# 02_Beam_Inputs.net
KiCad netlist of a schematic drawn in Altium Designer
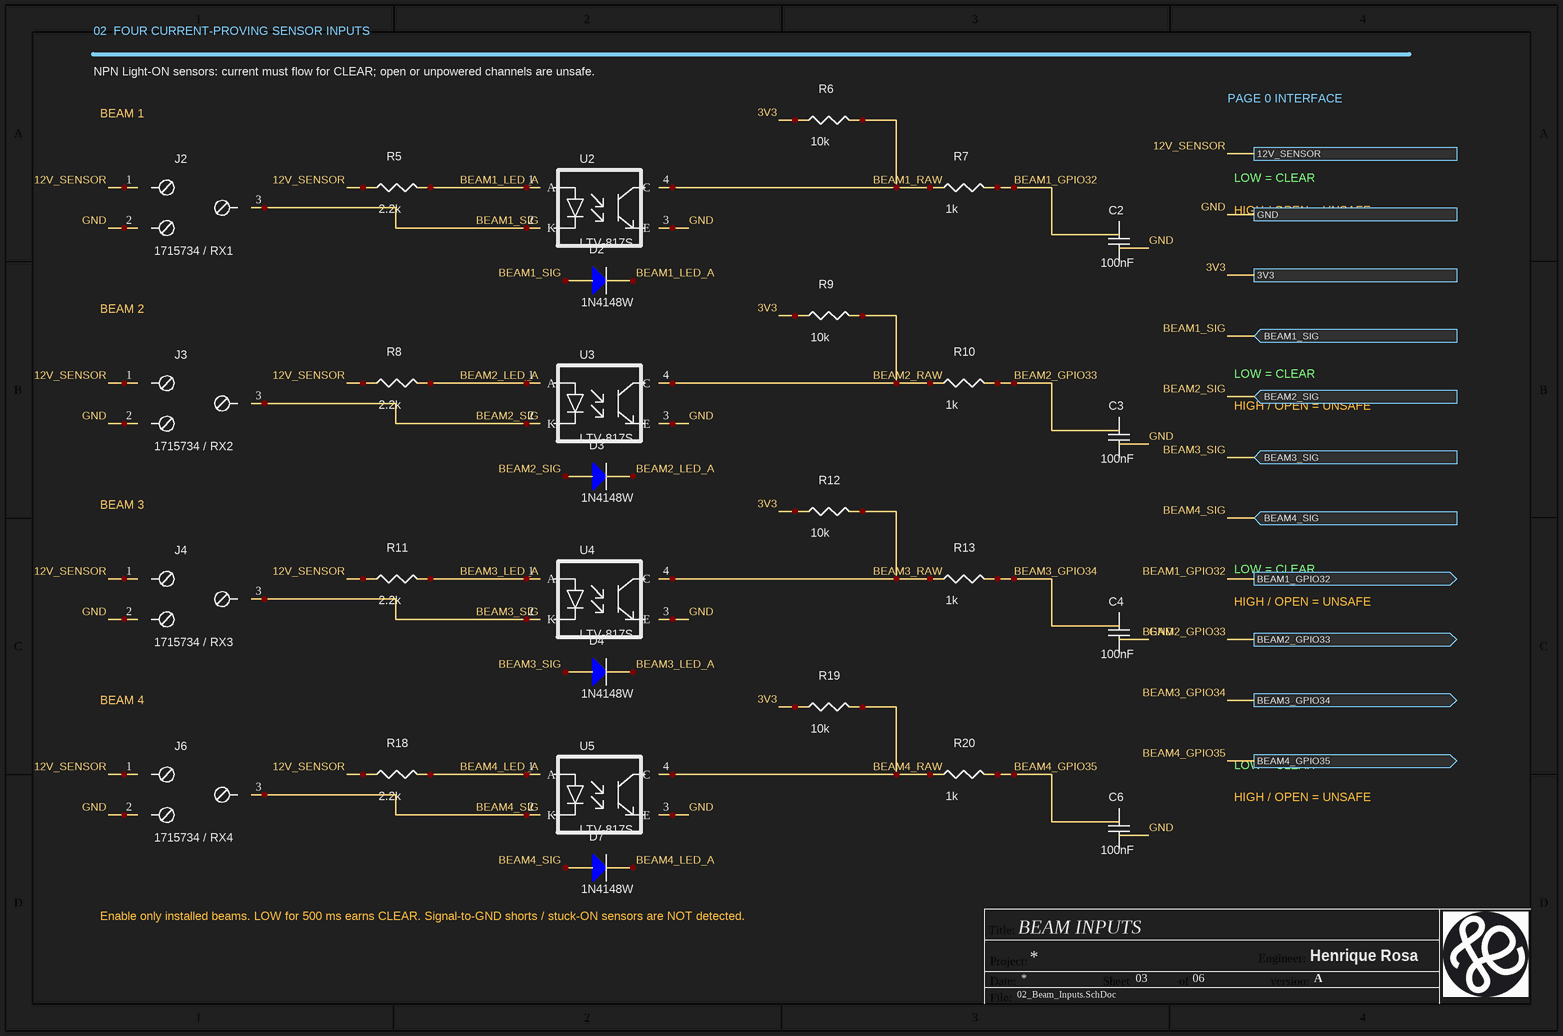
[diagram p0: 02_Beam_Inputs.SchDoc]

(export (version "E")
  (design (tool "Eeschema 10.0.6"))
  (components
    (comp (ref "C2")
      (value "100nF")
      (footprint "PCB - CAPACITOR - MLCC - MURATA GRM21B 0805_2012:MURATA GRM21B 0805_2012")
      (description "Input RC filter")
      (fields
        (field (name "MANUFACTURER") "Murata")
        (field (name "MANUFACTURER PART NUMBER") "GRM21BR71H104KA01L")
      )
      (libsource (lib "Miscellaneous Devices") (part "GRM21BR71H104KA01L"))
    )
    (comp (ref "C3")
      (value "100nF")
      (footprint "PCB - CAPACITOR - MLCC - MURATA GRM21B 0805_2012:MURATA GRM21B 0805_2012")
      (description "Input RC filter")
      (fields
        (field (name "MANUFACTURER") "Murata")
        (field (name "MANUFACTURER PART NUMBER") "GRM21BR71H104KA01L")
      )
      (libsource (lib "Miscellaneous Devices") (part "GRM21BR71H104KA01L"))
    )
    (comp (ref "C4")
      (value "100nF")
      (footprint "PCB - CAPACITOR - MLCC - MURATA GRM21B 0805_2012:MURATA GRM21B 0805_2012")
      (description "Input RC filter")
      (fields
        (field (name "MANUFACTURER") "Murata")
        (field (name "MANUFACTURER PART NUMBER") "GRM21BR71H104KA01L")
      )
      (libsource (lib "Miscellaneous Devices") (part "GRM21BR71H104KA01L"))
    )
    (comp (ref "C6")
      (value "100nF")
      (footprint "PCB - CAPACITOR - MLCC - MURATA GRM21B 0805_2012:MURATA GRM21B 0805_2012")
      (description "Input RC filter")
      (fields
        (field (name "MANUFACTURER") "Murata")
        (field (name "MANUFACTURER PART NUMBER") "GRM21BR71H104KA01L")
      )
      (libsource (lib "Miscellaneous Devices") (part "GRM21BR71H104KA01L"))
    )
    (comp (ref "D2")
      (value "1N4148W")
      (footprint "PinRepairFootprints:1N4148W_SOD123_A1_K2")
      (description "Reverse clamp: A to SIG; K to opto LED anode")
      (fields (field (name "PART NUMBER") "FDLL4148") (field (name "MANUFACTURER") "Nexperia"))
      (libsource (lib "Miscellaneous Devices") (part "1N4148W"))
    )
    (comp (ref "D3")
      (value "1N4148W")
      (footprint "PinRepairFootprints:1N4148W_SOD123_A1_K2")
      (description "Reverse clamp: A to SIG; K to opto LED anode")
      (fields (field (name "PART NUMBER") "FDLL4148") (field (name "MANUFACTURER") "Nexperia"))
      (libsource (lib "Miscellaneous Devices") (part "1N4148W"))
    )
    (comp (ref "D4")
      (value "1N4148W")
      (footprint "PinRepairFootprints:1N4148W_SOD123_A1_K2")
      (description "Reverse clamp: A to SIG; K to opto LED anode")
      (fields (field (name "PART NUMBER") "FDLL4148") (field (name "MANUFACTURER") "Nexperia"))
      (libsource (lib "Miscellaneous Devices") (part "1N4148W"))
    )
    (comp (ref "D7")
      (value "1N4148W")
      (footprint "PinRepairFootprints:1N4148W_SOD123_A1_K2")
      (description "Reverse clamp: A to SIG; K to opto LED anode")
      (fields (field (name "PART NUMBER") "FDLL4148") (field (name "MANUFACTURER") "Nexperia"))
      (libsource (lib "Miscellaneous Devices") (part "1N4148W"))
    )
    (comp (ref "J2")
      (value "1715734 / RX1")
      (footprint "OpticalHardware:PHOENIX_1715734_MKDS_3_508")
      (description "12V / GND / NPN signal terminal")
      (fields
        (field (name "MANUFACTURER") "Phoenix Contact")
        (field (name "MANUFACTURER PART NUMBER") "1715734")
      )
      (libsource (lib "PartSpecificComponents") (part "PHOENIX_1715734"))
    )
    (comp (ref "J3")
      (value "1715734 / RX2")
      (footprint "OpticalHardware:PHOENIX_1715734_MKDS_3_508")
      (description "12V / GND / NPN signal terminal")
      (fields
        (field (name "MANUFACTURER") "Phoenix Contact")
        (field (name "MANUFACTURER PART NUMBER") "1715734")
      )
      (libsource (lib "PartSpecificComponents") (part "PHOENIX_1715734"))
    )
    (comp (ref "J4")
      (value "1715734 / RX3")
      (footprint "OpticalHardware:PHOENIX_1715734_MKDS_3_508")
      (description "12V / GND / NPN signal terminal")
      (fields
        (field (name "MANUFACTURER") "Phoenix Contact")
        (field (name "MANUFACTURER PART NUMBER") "1715734")
      )
      (libsource (lib "PartSpecificComponents") (part "PHOENIX_1715734"))
    )
    (comp (ref "J6")
      (value "1715734 / RX4")
      (footprint "OpticalHardware:PHOENIX_1715734_MKDS_3_508")
      (description "12V / GND / NPN signal terminal")
      (fields
        (field (name "MANUFACTURER") "Phoenix Contact")
        (field (name "MANUFACTURER PART NUMBER") "1715734")
      )
      (libsource (lib "PartSpecificComponents") (part "PHOENIX_1715734"))
    )
    (comp (ref "R5")
      (value "2.2k")
      (footprint "PCB - RESISTOR - CHIP - YAGEO RES 0805_2012:YAGEO RES 0805_2012")
      (description "Optocoupler LED current limit")
      (fields
        (field (name "MANUFACTURER") "Yageo")
        (field (name "MANUFACTURER PART NUMBER") "RC0805FR-072K2L")
      )
      (libsource (lib "Miscellaneous Devices") (part "RC0805FR-072K2L"))
    )
    (comp (ref "R6")
      (value "10k")
      (footprint "PCB - RESISTOR - CHIP - YAGEO RES 0805_2012:YAGEO RES 0805_2012")
      (description "Pull-up earns unsafe if optocoupler is off")
      (fields
        (field (name "MANUFACTURER") "Yageo")
        (field (name "MANUFACTURER PART NUMBER") "RC0805FR-0710KL")
      )
      (libsource (lib "Miscellaneous Devices") (part "RC0805FR-0710KL"))
    )
    (comp (ref "R7")
      (value "1k")
      (footprint "PCB - RESISTOR - CHIP - YAGEO RES 0805_2012:YAGEO RES 0805_2012")
      (description "Input current limit")
      (fields
        (field (name "MANUFACTURER") "Yageo")
        (field (name "MANUFACTURER PART NUMBER") "RC0805FR-071KL")
      )
      (libsource (lib "Miscellaneous Devices") (part "RC0805FR-071KL"))
    )
    (comp (ref "R8")
      (value "2.2k")
      (footprint "PCB - RESISTOR - CHIP - YAGEO RES 0805_2012:YAGEO RES 0805_2012")
      (description "Optocoupler LED current limit")
      (fields
        (field (name "MANUFACTURER") "Yageo")
        (field (name "MANUFACTURER PART NUMBER") "RC0805FR-072K2L")
      )
      (libsource (lib "Miscellaneous Devices") (part "RC0805FR-072K2L"))
    )
    (comp (ref "R9")
      (value "10k")
      (footprint "PCB - RESISTOR - CHIP - YAGEO RES 0805_2012:YAGEO RES 0805_2012")
      (description "Pull-up earns unsafe if optocoupler is off")
      (fields
        (field (name "MANUFACTURER") "Yageo")
        (field (name "MANUFACTURER PART NUMBER") "RC0805FR-0710KL")
      )
      (libsource (lib "Miscellaneous Devices") (part "RC0805FR-0710KL"))
    )
    (comp (ref "R10")
      (value "1k")
      (footprint "PCB - RESISTOR - CHIP - YAGEO RES 0805_2012:YAGEO RES 0805_2012")
      (description "Input current limit")
      (fields
        (field (name "MANUFACTURER") "Yageo")
        (field (name "MANUFACTURER PART NUMBER") "RC0805FR-071KL")
      )
      (libsource (lib "Miscellaneous Devices") (part "RC0805FR-071KL"))
    )
    (comp (ref "R11")
      (value "2.2k")
      (footprint "PCB - RESISTOR - CHIP - YAGEO RES 0805_2012:YAGEO RES 0805_2012")
      (description "Optocoupler LED current limit")
      (fields
        (field (name "MANUFACTURER") "Yageo")
        (field (name "MANUFACTURER PART NUMBER") "RC0805FR-072K2L")
      )
      (libsource (lib "Miscellaneous Devices") (part "RC0805FR-072K2L"))
    )
    (comp (ref "R12")
      (value "10k")
      (footprint "PCB - RESISTOR - CHIP - YAGEO RES 0805_2012:YAGEO RES 0805_2012")
      (description "Pull-up earns unsafe if optocoupler is off")
      (fields
        (field (name "MANUFACTURER") "Yageo")
        (field (name "MANUFACTURER PART NUMBER") "RC0805FR-0710KL")
      )
      (libsource (lib "Miscellaneous Devices") (part "RC0805FR-0710KL"))
    )
    (comp (ref "R13")
      (value "1k")
      (footprint "PCB - RESISTOR - CHIP - YAGEO RES 0805_2012:YAGEO RES 0805_2012")
      (description "Input current limit")
      (fields
        (field (name "MANUFACTURER") "Yageo")
        (field (name "MANUFACTURER PART NUMBER") "RC0805FR-071KL")
      )
      (libsource (lib "Miscellaneous Devices") (part "RC0805FR-071KL"))
    )
    (comp (ref "R18")
      (value "2.2k")
      (footprint "PCB - RESISTOR - CHIP - YAGEO RES 0805_2012:YAGEO RES 0805_2012")
      (description "Optocoupler LED current limit")
      (fields
        (field (name "MANUFACTURER") "Yageo")
        (field (name "MANUFACTURER PART NUMBER") "RC0805FR-072K2L")
      )
      (libsource (lib "Miscellaneous Devices") (part "RC0805FR-072K2L"))
    )
    (comp (ref "R19")
      (value "10k")
      (footprint "PCB - RESISTOR - CHIP - YAGEO RES 0805_2012:YAGEO RES 0805_2012")
      (description "Pull-up earns unsafe if optocoupler is off")
      (fields
        (field (name "MANUFACTURER") "Yageo")
        (field (name "MANUFACTURER PART NUMBER") "RC0805FR-0710KL")
      )
      (libsource (lib "Miscellaneous Devices") (part "RC0805FR-0710KL"))
    )
    (comp (ref "R20")
      (value "1k")
      (footprint "PCB - RESISTOR - CHIP - YAGEO RES 0805_2012:YAGEO RES 0805_2012")
      (description "Input current limit")
      (fields
        (field (name "MANUFACTURER") "Yageo")
        (field (name "MANUFACTURER PART NUMBER") "RC0805FR-071KL")
      )
      (libsource (lib "Miscellaneous Devices") (part "RC0805FR-071KL"))
    )
    (comp (ref "U2")
      (value "LTV-817S")
      (footprint "PCB - OPTOISOLATOR - LITEON LTV-817:LITEON LTV-817")
      (description "Phototransistor optocoupler")
      (fields
        (field (name "MANUFACTURER") "Lite-On")
        (field (name "MANUFACTURER PART NUMBER") "LTV-817S-TA1")
      )
      (libsource (lib "*") (part "LTV-817S-TA1"))
    )
    (comp (ref "U3")
      (value "LTV-817S")
      (footprint "PCB - OPTOISOLATOR - LITEON LTV-817:LITEON LTV-817")
      (description "Phototransistor optocoupler")
      (fields
        (field (name "MANUFACTURER") "Lite-On")
        (field (name "MANUFACTURER PART NUMBER") "LTV-817S-TA1")
      )
      (libsource (lib "*") (part "LTV-817S-TA1"))
    )
    (comp (ref "U4")
      (value "LTV-817S")
      (footprint "PCB - OPTOISOLATOR - LITEON LTV-817:LITEON LTV-817")
      (description "Phototransistor optocoupler")
      (fields
        (field (name "MANUFACTURER") "Lite-On")
        (field (name "MANUFACTURER PART NUMBER") "LTV-817S-TA1")
      )
      (libsource (lib "*") (part "LTV-817S-TA1"))
    )
    (comp (ref "U5")
      (value "LTV-817S")
      (footprint "PCB - OPTOISOLATOR - LITEON LTV-817:LITEON LTV-817")
      (description "Phototransistor optocoupler")
      (fields
        (field (name "MANUFACTURER") "Lite-On")
        (field (name "MANUFACTURER PART NUMBER") "LTV-817S-TA1")
      )
      (libsource (lib "*") (part "LTV-817S-TA1"))
    )
  )
  (nets
    (net (code "1") (name "/3V3") (class "Default")
      (node (ref "R12") (pin "1") (pinfunction "1_1") (pintype "passive"))
      (node (ref "R19") (pin "1") (pinfunction "1_1") (pintype "passive"))
      (node (ref "R6") (pin "1") (pinfunction "1_1") (pintype "passive"))
      (node (ref "R9") (pin "1") (pinfunction "1_1") (pintype "passive"))
    )
    (net (code "2") (name "/12V_SENSOR") (class "Default")
      (node (ref "J2") (pin "1") (pinfunction "+12V_1") (pintype "passive"))
      (node (ref "J3") (pin "1") (pinfunction "+12V_1") (pintype "passive"))
      (node (ref "J4") (pin "1") (pinfunction "+12V_1") (pintype "passive"))
      (node (ref "J6") (pin "1") (pinfunction "+12V_1") (pintype "passive"))
      (node (ref "R11") (pin "1") (pinfunction "1_1") (pintype "passive"))
      (node (ref "R18") (pin "1") (pinfunction "1_1") (pintype "passive"))
      (node (ref "R5") (pin "1") (pinfunction "1_1") (pintype "passive"))
      (node (ref "R8") (pin "1") (pinfunction "1_1") (pintype "passive"))
    )
    (net (code "3") (name "/BEAM1_GPIO32") (class "Default")
      (node (ref "R7") (pin "2") (pinfunction "2_2") (pintype "passive"))
    )
    (net (code "4") (name "/BEAM1_LED_A") (class "Default")
      (node (ref "D2") (pin "2") (pinfunction "K_2") (pintype "passive"))
      (node (ref "R5") (pin "2") (pinfunction "2_2") (pintype "passive"))
      (node (ref "U2") (pin "1") (pinfunction "A_1") (pintype "passive"))
    )
    (net (code "5") (name "/BEAM1_RAW") (class "Default")
      (node (ref "R6") (pin "2") (pinfunction "2_2") (pintype "passive"))
      (node (ref "R7") (pin "1") (pinfunction "1_1") (pintype "passive"))
      (node (ref "U2") (pin "4") (pinfunction "C_4") (pintype "open_collector"))
    )
    (net (code "6") (name "/BEAM1_SIG") (class "Default")
      (node (ref "D2") (pin "1") (pinfunction "A_1") (pintype "passive"))
      (node (ref "J2") (pin "3") (pinfunction "OUT_3") (pintype "passive"))
      (node (ref "U2") (pin "2") (pinfunction "K_2") (pintype "passive"))
    )
    (net (code "7") (name "/BEAM2_GPIO33") (class "Default")
      (node (ref "R10") (pin "2") (pinfunction "2_2") (pintype "passive"))
    )
    (net (code "8") (name "/BEAM2_LED_A") (class "Default")
      (node (ref "D3") (pin "2") (pinfunction "K_2") (pintype "passive"))
      (node (ref "R8") (pin "2") (pinfunction "2_2") (pintype "passive"))
      (node (ref "U3") (pin "1") (pinfunction "A_1") (pintype "passive"))
    )
    (net (code "9") (name "/BEAM2_RAW") (class "Default")
      (node (ref "R10") (pin "1") (pinfunction "1_1") (pintype "passive"))
      (node (ref "R9") (pin "2") (pinfunction "2_2") (pintype "passive"))
      (node (ref "U3") (pin "4") (pinfunction "C_4") (pintype "open_collector"))
    )
    (net (code "10") (name "/BEAM2_SIG") (class "Default")
      (node (ref "D3") (pin "1") (pinfunction "A_1") (pintype "passive"))
      (node (ref "J3") (pin "3") (pinfunction "OUT_3") (pintype "passive"))
      (node (ref "U3") (pin "2") (pinfunction "K_2") (pintype "passive"))
    )
    (net (code "11") (name "/BEAM3_GPIO34") (class "Default")
      (node (ref "R13") (pin "2") (pinfunction "2_2") (pintype "passive"))
    )
    (net (code "12") (name "/BEAM3_LED_A") (class "Default")
      (node (ref "D4") (pin "2") (pinfunction "K_2") (pintype "passive"))
      (node (ref "R11") (pin "2") (pinfunction "2_2") (pintype "passive"))
      (node (ref "U4") (pin "1") (pinfunction "A_1") (pintype "passive"))
    )
    (net (code "13") (name "/BEAM3_RAW") (class "Default")
      (node (ref "R12") (pin "2") (pinfunction "2_2") (pintype "passive"))
      (node (ref "R13") (pin "1") (pinfunction "1_1") (pintype "passive"))
      (node (ref "U4") (pin "4") (pinfunction "C_4") (pintype "open_collector"))
    )
    (net (code "14") (name "/BEAM3_SIG") (class "Default")
      (node (ref "D4") (pin "1") (pinfunction "A_1") (pintype "passive"))
      (node (ref "J4") (pin "3") (pinfunction "OUT_3") (pintype "passive"))
      (node (ref "U4") (pin "2") (pinfunction "K_2") (pintype "passive"))
    )
    (net (code "15") (name "/BEAM4_GPIO35") (class "Default")
      (node (ref "R20") (pin "2") (pinfunction "2_2") (pintype "passive"))
    )
    (net (code "16") (name "/BEAM4_LED_A") (class "Default")
      (node (ref "D7") (pin "2") (pinfunction "K_2") (pintype "passive"))
      (node (ref "R18") (pin "2") (pinfunction "2_2") (pintype "passive"))
      (node (ref "U5") (pin "1") (pinfunction "A_1") (pintype "passive"))
    )
    (net (code "17") (name "/BEAM4_RAW") (class "Default")
      (node (ref "R19") (pin "2") (pinfunction "2_2") (pintype "passive"))
      (node (ref "R20") (pin "1") (pinfunction "1_1") (pintype "passive"))
      (node (ref "U5") (pin "4") (pinfunction "C_4") (pintype "open_collector"))
    )
    (net (code "18") (name "/BEAM4_SIG") (class "Default")
      (node (ref "D7") (pin "1") (pinfunction "A_1") (pintype "passive"))
      (node (ref "J6") (pin "3") (pinfunction "OUT_3") (pintype "passive"))
      (node (ref "U5") (pin "2") (pinfunction "K_2") (pintype "passive"))
    )
    (net (code "19") (name "/GND") (class "Default")
      (node (ref "J2") (pin "2") (pinfunction "0V_2") (pintype "passive"))
      (node (ref "J3") (pin "2") (pinfunction "0V_2") (pintype "passive"))
      (node (ref "J4") (pin "2") (pinfunction "0V_2") (pintype "passive"))
      (node (ref "J6") (pin "2") (pinfunction "0V_2") (pintype "passive"))
      (node (ref "U2") (pin "3") (pinfunction "E_3") (pintype "passive"))
      (node (ref "U3") (pin "3") (pinfunction "E_3") (pintype "passive"))
      (node (ref "U4") (pin "3") (pinfunction "E_3") (pintype "passive"))
      (node (ref "U5") (pin "3") (pinfunction "E_3") (pintype "passive"))
    )
    (net (code "20") (name "unconnected-(C2-Pad1)") (class "Default")
      (node (ref "C2") (pin "1") (pinfunction "1_1") (pintype "passive"))
    )
    (net (code "21") (name "unconnected-(C2-Pad2)") (class "Default")
      (node (ref "C2") (pin "2") (pinfunction "2_2") (pintype "passive"))
    )
    (net (code "22") (name "unconnected-(C3-Pad1)") (class "Default")
      (node (ref "C3") (pin "1") (pinfunction "1_1") (pintype "passive"))
    )
    (net (code "23") (name "unconnected-(C3-Pad2)") (class "Default")
      (node (ref "C3") (pin "2") (pinfunction "2_2") (pintype "passive"))
    )
    (net (code "24") (name "unconnected-(C4-Pad1)") (class "Default")
      (node (ref "C4") (pin "1") (pinfunction "1_1") (pintype "passive"))
    )
    (net (code "25") (name "unconnected-(C4-Pad2)") (class "Default")
      (node (ref "C4") (pin "2") (pinfunction "2_2") (pintype "passive"))
    )
    (net (code "26") (name "unconnected-(C6-Pad1)") (class "Default")
      (node (ref "C6") (pin "1") (pinfunction "1_1") (pintype "passive"))
    )
    (net (code "27") (name "unconnected-(C6-Pad2)") (class "Default")
      (node (ref "C6") (pin "2") (pinfunction "2_2") (pintype "passive"))
    )
  )
)
